# crystal_oscillator_high_freq.net
KiCad netlist of a schematic drawn in Altium Designer
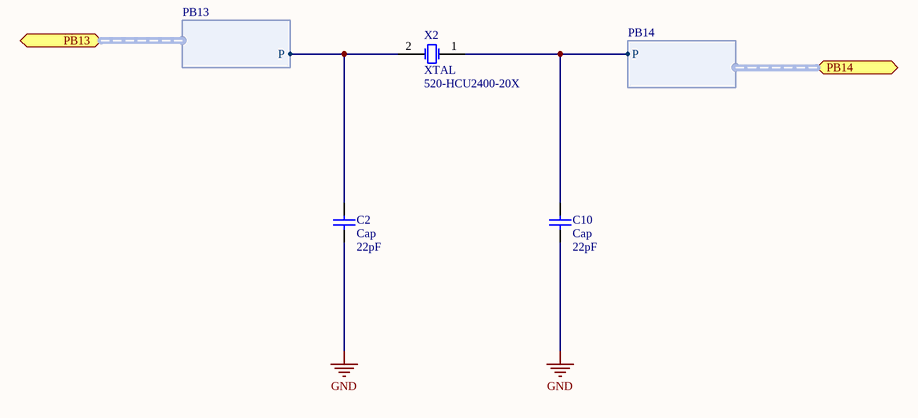
[diagram p0: crystal_oscillator_high_freq.SchDoc]

(export (version "E")
  (design (tool "Eeschema 10.0.6"))
  (components
    (comp (ref "C2")
      (value "Cap")
      (footprint "RAD-0.3")
      (description "Capacitor")
      (fields (field (name "ALTIUM_VALUE") "22pF") (field (name "PUBLISHER") "Altium Limited"))
      (libsource (lib "Miscellaneous Devices") (part "Cap"))
    )
    (comp (ref "C10")
      (value "Cap")
      (footprint "RAD-0.3")
      (description "Capacitor")
      (fields (field (name "ALTIUM_VALUE") "22pF") (field (name "PUBLISHER") "Altium Limited"))
      (libsource (lib "Miscellaneous Devices") (part "Cap"))
    )
    (comp (ref "X2")
      (value "XTAL")
      (footprint "R38")
      (description "Crystal Oscillator")
      (fields
        (field (name "SUPPLIER PART NUMBER 1") "520-HCU2400-20X")
        (field (name "MANUFACTURER") "ECS")
        (field (name "MANUFACTURER PART NUMBER") "ECS-240-20-4X")
        (field (name "PUBLISHER") "Altium Limited")
      )
      (libsource (lib "Miscellaneous Devices") (part "XTAL"))
    )
  )
  (nets
    (net (code "5") (name "GND") (class "Default")
      (node (ref "C10") (pin "1") (pinfunction "1_1") (pintype "passive"))
      (node (ref "C2") (pin "1") (pinfunction "1_1") (pintype "passive"))
    )
    (net (code "6") (name "Net-(X2-OSC1)") (class "Default")
      (node (ref "C10") (pin "2") (pinfunction "2_2") (pintype "passive"))
      (node (ref "X2") (pin "1") (pinfunction "OSC1_1") (pintype "passive"))
    )
    (net (code "7") (name "Net-(X2-OSC2)") (class "Default")
      (node (ref "C2") (pin "2") (pinfunction "2_2") (pintype "passive"))
      (node (ref "X2") (pin "2") (pinfunction "OSC2_2") (pintype "passive"))
    )
  )
)
